# Key_Panel_030602.net
KiCad netlist of a schematic drawn in Altium Designer
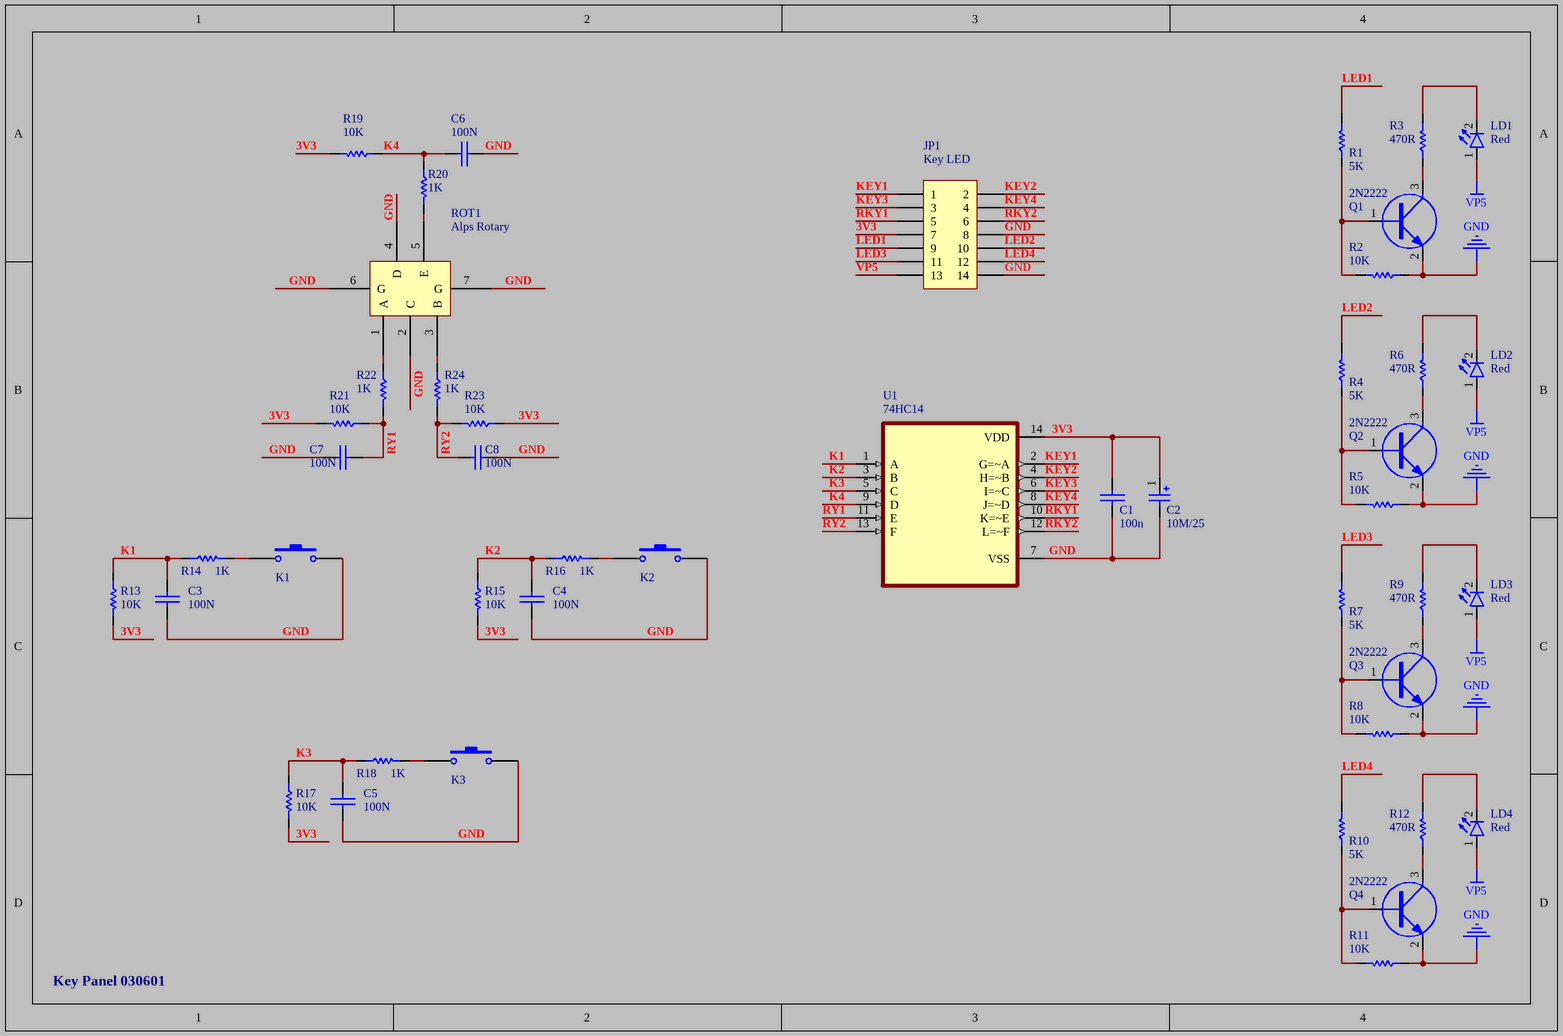
[diagram p0: Key Panel 030602.SchDoc]

(export (version "E")
  (design (tool "Eeschema 10.0.6"))
  (components
    (comp (ref "C1") (value "100n") (footprint "SMD_CAP_1206.") (libsource (lib "*") (part "C")))
    (comp (ref "C2")
      (value "10M/25")
      (footprint "CAP1p")
      (description "SMD Polarized Capacitor")
      (fields (field (name "PUBLISHER") "Altium Limited"))
      (libsource (lib "Mylibrary2019") (part "Cap Pol1 _ SMD"))
    )
    (comp (ref "C3") (value "100N") (footprint "SMD_CAP_1206.") (libsource (lib "*") (part "C")))
    (comp (ref "C4") (value "100N") (footprint "SMD_CAP_1206.") (libsource (lib "*") (part "C")))
    (comp (ref "C5") (value "100N") (footprint "SMD_CAP_1206.") (libsource (lib "*") (part "C")))
    (comp (ref "C6") (value "100N") (footprint "SMD_CAP_1206.") (libsource (lib "*") (part "C")))
    (comp (ref "C7") (value "100N") (footprint "SMD_CAP_1206.") (libsource (lib "*") (part "C")))
    (comp (ref "C8") (value "100N") (footprint "SMD_CAP_1206.") (libsource (lib "*") (part "C")))
    (comp (ref "JP1")
      (value "Key LED")
      (footprint "IDC14-BOX")
      (description "Header, 7-Pin, Dual row")
      (fields (field (name "PUBLISHER") "Altium Limited"))
      (libsource (lib "Miscellaneous Connectors") (part "Header 7X2"))
    )
    (comp (ref "K1")
      (value "Left")
      (footprint "SW-12*14")
      (description "Push Button Switch")
      (libsource (lib "My Library") (part "Switch PB"))
    )
    (comp (ref "K2")
      (value "Left")
      (footprint "SW-12*14")
      (description "Push Button Switch")
      (libsource (lib "My Library") (part "Switch PB"))
    )
    (comp (ref "K3")
      (value "Left")
      (footprint "SW-12*14")
      (description "Push Button Switch")
      (libsource (lib "My Library") (part "Switch PB"))
    )
    (comp (ref "LD1")
      (value "Red")
      (footprint "LED3")
      (description "LED")
      (fields (field (name "COLOR") "Red") (field (name "DESIGNER") "Saeid Jorablo"))
      (libsource (lib "My Library") (part "LED"))
    )
    (comp (ref "LD2")
      (value "Red")
      (footprint "LED3")
      (description "LED")
      (fields (field (name "COLOR") "Red") (field (name "DESIGNER") "Saeid Jorablo"))
      (libsource (lib "My Library") (part "LED"))
    )
    (comp (ref "LD3")
      (value "Red")
      (footprint "LED3")
      (description "LED")
      (fields (field (name "COLOR") "Red") (field (name "DESIGNER") "Saeid Jorablo"))
      (libsource (lib "My Library") (part "LED"))
    )
    (comp (ref "LD4")
      (value "Red")
      (footprint "LED3")
      (description "LED")
      (fields (field (name "COLOR") "Red") (field (name "DESIGNER") "Saeid Jorablo"))
      (libsource (lib "My Library") (part "LED"))
    )
    (comp (ref "Q1") (value "2N2222") (footprint "2N2222") (libsource (lib "1403 Schlib 2020") (part "N")))
    (comp (ref "Q2") (value "2N2222") (footprint "2N2222") (libsource (lib "1403 Schlib 2020") (part "N")))
    (comp (ref "Q3") (value "2N2222") (footprint "2N2222") (libsource (lib "1403 Schlib 2020") (part "N")))
    (comp (ref "Q4") (value "2N2222") (footprint "2N2222") (libsource (lib "1403 Schlib 2020") (part "N")))
    (comp (ref "R1")
      (value "5K")
      (footprint "RES 1206")
      (description "Resistor")
      (fields (field (name "TOLERANCE") "5%") (field (name "POWER") "1/8 W"))
      (libsource (lib "My Library") (part "Resistor"))
    )
    (comp (ref "R2")
      (value "10K")
      (footprint "RES 1206")
      (description "Resistor")
      (fields (field (name "TOLERANCE") "5%") (field (name "POWER") "1/8 W"))
      (libsource (lib "My Library") (part "Resistor"))
    )
    (comp (ref "R3")
      (value "470R")
      (footprint "RES 1206")
      (description "Resistor")
      (fields (field (name "TOLERANCE") "5%") (field (name "POWER") "1/8 W"))
      (libsource (lib "My Library") (part "Resistor"))
    )
    (comp (ref "R4")
      (value "5K")
      (footprint "RES 1206")
      (description "Resistor")
      (fields (field (name "TOLERANCE") "5%") (field (name "POWER") "1/8 W"))
      (libsource (lib "My Library") (part "Resistor"))
    )
    (comp (ref "R5")
      (value "10K")
      (footprint "RES 1206")
      (description "Resistor")
      (fields (field (name "TOLERANCE") "5%") (field (name "POWER") "1/8 W"))
      (libsource (lib "My Library") (part "Resistor"))
    )
    (comp (ref "R6")
      (value "470R")
      (footprint "RES 1206")
      (description "Resistor")
      (fields (field (name "TOLERANCE") "5%") (field (name "POWER") "1/8 W"))
      (libsource (lib "My Library") (part "Resistor"))
    )
    (comp (ref "R7")
      (value "5K")
      (footprint "RES 1206")
      (description "Resistor")
      (fields (field (name "TOLERANCE") "5%") (field (name "POWER") "1/8 W"))
      (libsource (lib "My Library") (part "Resistor"))
    )
    (comp (ref "R8")
      (value "10K")
      (footprint "RES 1206")
      (description "Resistor")
      (fields (field (name "TOLERANCE") "5%") (field (name "POWER") "1/8 W"))
      (libsource (lib "My Library") (part "Resistor"))
    )
    (comp (ref "R9")
      (value "470R")
      (footprint "RES 1206")
      (description "Resistor")
      (fields (field (name "TOLERANCE") "5%") (field (name "POWER") "1/8 W"))
      (libsource (lib "My Library") (part "Resistor"))
    )
    (comp (ref "R10")
      (value "5K")
      (footprint "RES 1206")
      (description "Resistor")
      (fields (field (name "TOLERANCE") "5%") (field (name "POWER") "1/8 W"))
      (libsource (lib "My Library") (part "Resistor"))
    )
    (comp (ref "R11")
      (value "10K")
      (footprint "RES 1206")
      (description "Resistor")
      (fields (field (name "TOLERANCE") "5%") (field (name "POWER") "1/8 W"))
      (libsource (lib "My Library") (part "Resistor"))
    )
    (comp (ref "R12")
      (value "470R")
      (footprint "RES 1206")
      (description "Resistor")
      (fields (field (name "TOLERANCE") "5%") (field (name "POWER") "1/8 W"))
      (libsource (lib "My Library") (part "Resistor"))
    )
    (comp (ref "R13")
      (value "10K")
      (footprint "RES 1206")
      (description "Resistor")
      (fields (field (name "TOLERANCE") "5%") (field (name "POWER") "1/8 W"))
      (libsource (lib "My Library") (part "Resistor"))
    )
    (comp (ref "R14")
      (value "1K")
      (footprint "RES 1206")
      (description "Resistor")
      (fields (field (name "TOLERANCE") "5%") (field (name "POWER") "1/8 W"))
      (libsource (lib "My Library") (part "Resistor"))
    )
    (comp (ref "R15")
      (value "10K")
      (footprint "RES 1206")
      (description "Resistor")
      (fields (field (name "TOLERANCE") "5%") (field (name "POWER") "1/8 W"))
      (libsource (lib "My Library") (part "Resistor"))
    )
    (comp (ref "R16")
      (value "1K")
      (footprint "RES 1206")
      (description "Resistor")
      (fields (field (name "TOLERANCE") "5%") (field (name "POWER") "1/8 W"))
      (libsource (lib "My Library") (part "Resistor"))
    )
    (comp (ref "R17")
      (value "10K")
      (footprint "RES 1206")
      (description "Resistor")
      (fields (field (name "TOLERANCE") "5%") (field (name "POWER") "1/8 W"))
      (libsource (lib "My Library") (part "Resistor"))
    )
    (comp (ref "R18")
      (value "1K")
      (footprint "RES 1206")
      (description "Resistor")
      (fields (field (name "TOLERANCE") "5%") (field (name "POWER") "1/8 W"))
      (libsource (lib "My Library") (part "Resistor"))
    )
    (comp (ref "R19")
      (value "10K")
      (footprint "RES 1206")
      (description "Resistor")
      (fields (field (name "TOLERANCE") "5%") (field (name "POWER") "1/8 W"))
      (libsource (lib "My Library") (part "Resistor"))
    )
    (comp (ref "R20")
      (value "1K")
      (footprint "RES 1206")
      (description "Resistor")
      (fields (field (name "TOLERANCE") "5%") (field (name "POWER") "1/8 W"))
      (libsource (lib "My Library") (part "Resistor"))
    )
    (comp (ref "R21")
      (value "10K")
      (footprint "RES 1206")
      (description "Resistor")
      (fields (field (name "TOLERANCE") "5%") (field (name "POWER") "1/8 W"))
      (libsource (lib "My Library") (part "Resistor"))
    )
    (comp (ref "R22")
      (value "1K")
      (footprint "RES 1206")
      (description "Resistor")
      (fields (field (name "TOLERANCE") "5%") (field (name "POWER") "1/8 W"))
      (libsource (lib "My Library") (part "Resistor"))
    )
    (comp (ref "R23")
      (value "10K")
      (footprint "RES 1206")
      (description "Resistor")
      (fields (field (name "TOLERANCE") "5%") (field (name "POWER") "1/8 W"))
      (libsource (lib "My Library") (part "Resistor"))
    )
    (comp (ref "R24")
      (value "1K")
      (footprint "RES 1206")
      (description "Resistor")
      (fields (field (name "TOLERANCE") "5%") (field (name "POWER") "1/8 W"))
      (libsource (lib "My Library") (part "Resistor"))
    )
    (comp (ref "ROT1")
      (value "Alps Rotary")
      (footprint "EC11")
      (libsource (lib "MyAltiumLib95") (part "AlpsRotary"))
    )
    (comp (ref "U1")
      (value "74HC14")
      (footprint "SOIC-14PIN")
      (description "CMOS Hex Schmitt Triggers 14-PDIP -55 to 125")
      (fields (field (name "MF") "Texas Instruments") (field (name "MP") "CD40106BE"))
      (libsource (lib "CD40106BE") (part "CD40106BE"))
    )
  )
  (nets
    (net (code "1") (name "/3V3") (class "Default")
      (node (ref "C1") (pin "2") (pintype "passive"))
      (node (ref "C2") (pin "1") (pinfunction "1_1") (pintype "passive"))
      (node (ref "JP1") (pin "7") (pinfunction "7_7") (pintype "passive"))
      (node (ref "R13") (pin "2") (pinfunction "2_2") (pintype "passive"))
      (node (ref "R15") (pin "2") (pinfunction "2_2") (pintype "passive"))
      (node (ref "R17") (pin "2") (pinfunction "2_2") (pintype "passive"))
      (node (ref "R19") (pin "2") (pinfunction "2_2") (pintype "passive"))
      (node (ref "R21") (pin "2") (pinfunction "2_2") (pintype "passive"))
      (node (ref "R23") (pin "1") (pinfunction "1_1") (pintype "passive"))
      (node (ref "U1") (pin "14") (pinfunction "VDD_14") (pintype "power_in"))
    )
    (net (code "2") (name "/K1") (class "Default")
      (node (ref "C3") (pin "2") (pintype "passive"))
      (node (ref "R13") (pin "1") (pinfunction "1_1") (pintype "passive"))
      (node (ref "R14") (pin "1") (pinfunction "1_1") (pintype "passive"))
      (node (ref "U1") (pin "1") (pinfunction "A_1") (pintype "input"))
    )
    (net (code "3") (name "/K2") (class "Default")
      (node (ref "C4") (pin "2") (pintype "passive"))
      (node (ref "R15") (pin "1") (pinfunction "1_1") (pintype "passive"))
      (node (ref "R16") (pin "1") (pinfunction "1_1") (pintype "passive"))
      (node (ref "U1") (pin "3") (pinfunction "B_3") (pintype "input"))
    )
    (net (code "4") (name "/K3") (class "Default")
      (node (ref "C5") (pin "2") (pintype "passive"))
      (node (ref "R17") (pin "1") (pinfunction "1_1") (pintype "passive"))
      (node (ref "R18") (pin "1") (pinfunction "1_1") (pintype "passive"))
      (node (ref "U1") (pin "5") (pinfunction "C_5") (pintype "input"))
    )
    (net (code "5") (name "/K4") (class "Default")
      (node (ref "C6") (pin "2") (pintype "passive"))
      (node (ref "R19") (pin "1") (pinfunction "1_1") (pintype "passive"))
      (node (ref "R20") (pin "1") (pinfunction "1_1") (pintype "passive"))
      (node (ref "U1") (pin "9") (pinfunction "D_9") (pintype "input"))
    )
    (net (code "6") (name "/KEY1") (class "Default")
      (node (ref "JP1") (pin "1") (pinfunction "1_1") (pintype "passive"))
      (node (ref "U1") (pin "2") (pinfunction "G=~A_2") (pintype "output"))
    )
    (net (code "7") (name "/KEY2") (class "Default")
      (node (ref "JP1") (pin "2") (pinfunction "2_2") (pintype "passive"))
      (node (ref "U1") (pin "4") (pinfunction "H=~B_4") (pintype "output"))
    )
    (net (code "8") (name "/KEY3") (class "Default")
      (node (ref "JP1") (pin "3") (pinfunction "3_3") (pintype "passive"))
      (node (ref "U1") (pin "6") (pinfunction "I=~C_6") (pintype "output"))
    )
    (net (code "9") (name "/KEY4") (class "Default")
      (node (ref "JP1") (pin "4") (pinfunction "4_4") (pintype "passive"))
      (node (ref "U1") (pin "8") (pinfunction "J=~D_8") (pintype "output"))
    )
    (net (code "10") (name "/LED1") (class "Default")
      (node (ref "JP1") (pin "9") (pinfunction "9_9") (pintype "passive"))
      (node (ref "R1") (pin "2") (pinfunction "2_2") (pintype "passive"))
    )
    (net (code "11") (name "/LED2") (class "Default")
      (node (ref "JP1") (pin "10") (pinfunction "10_10") (pintype "passive"))
      (node (ref "R4") (pin "2") (pinfunction "2_2") (pintype "passive"))
    )
    (net (code "12") (name "/LED3") (class "Default")
      (node (ref "JP1") (pin "11") (pinfunction "11_11") (pintype "passive"))
      (node (ref "R7") (pin "2") (pinfunction "2_2") (pintype "passive"))
    )
    (net (code "13") (name "/LED4") (class "Default")
      (node (ref "JP1") (pin "12") (pinfunction "12_12") (pintype "passive"))
      (node (ref "R10") (pin "2") (pinfunction "2_2") (pintype "passive"))
    )
    (net (code "14") (name "/RKY1") (class "Default")
      (node (ref "JP1") (pin "5") (pinfunction "5_5") (pintype "passive"))
      (node (ref "U1") (pin "10") (pinfunction "K=~E_10") (pintype "output"))
    )
    (net (code "15") (name "/RKY2") (class "Default")
      (node (ref "JP1") (pin "6") (pinfunction "6_6") (pintype "passive"))
      (node (ref "U1") (pin "12") (pinfunction "L=~F_12") (pintype "output"))
    )
    (net (code "16") (name "/RY1") (class "Default")
      (node (ref "C7") (pin "2") (pintype "passive"))
      (node (ref "R21") (pin "1") (pinfunction "1_1") (pintype "passive"))
      (node (ref "R22") (pin "2") (pinfunction "2_2") (pintype "passive"))
      (node (ref "U1") (pin "11") (pinfunction "E_11") (pintype "input"))
    )
    (net (code "17") (name "/RY2") (class "Default")
      (node (ref "C8") (pin "2") (pintype "passive"))
      (node (ref "R23") (pin "2") (pinfunction "2_2") (pintype "passive"))
      (node (ref "R24") (pin "2") (pinfunction "2_2") (pintype "passive"))
      (node (ref "U1") (pin "13") (pinfunction "F_13") (pintype "input"))
    )
    (net (code "18") (name "GND") (class "Default")
      (node (ref "C1") (pin "1") (pintype "passive"))
      (node (ref "C2") (pin "2") (pinfunction "2_2") (pintype "passive"))
      (node (ref "C3") (pin "1") (pintype "passive"))
      (node (ref "C4") (pin "1") (pintype "passive"))
      (node (ref "C5") (pin "1") (pintype "passive"))
      (node (ref "C6") (pin "1") (pintype "passive"))
      (node (ref "C7") (pin "1") (pintype "passive"))
      (node (ref "C8") (pin "1") (pintype "passive"))
      (node (ref "JP1") (pin "14") (pinfunction "14_14") (pintype "passive"))
      (node (ref "JP1") (pin "8") (pinfunction "8_8") (pintype "passive"))
      (node (ref "K1") (pin "2") (pinfunction "2_2") (pintype "passive"))
      (node (ref "K2") (pin "2") (pinfunction "2_2") (pintype "passive"))
      (node (ref "K3") (pin "2") (pinfunction "2_2") (pintype "passive"))
      (node (ref "Q1") (pin "2") (pinfunction "B_2") (pintype "passive"))
      (node (ref "Q2") (pin "2") (pinfunction "B_2") (pintype "passive"))
      (node (ref "Q3") (pin "2") (pinfunction "B_2") (pintype "passive"))
      (node (ref "Q4") (pin "2") (pinfunction "B_2") (pintype "passive"))
      (node (ref "R11") (pin "1") (pinfunction "1_1") (pintype "passive"))
      (node (ref "R2") (pin "1") (pinfunction "1_1") (pintype "passive"))
      (node (ref "R5") (pin "1") (pinfunction "1_1") (pintype "passive"))
      (node (ref "R8") (pin "1") (pinfunction "1_1") (pintype "passive"))
      (node (ref "ROT1") (pin "2") (pinfunction "C_2") (pintype "passive"))
      (node (ref "ROT1") (pin "4") (pinfunction "D_4") (pintype "passive"))
      (node (ref "ROT1") (pin "6") (pinfunction "G_6") (pintype "passive"))
      (node (ref "ROT1") (pin "7") (pinfunction "G_7") (pintype "passive"))
      (node (ref "U1") (pin "7") (pinfunction "VSS_7") (pintype "power_in"))
    )
    (net (code "19") (name "Net-(K1-Pad1)") (class "Default")
      (node (ref "K1") (pin "1") (pinfunction "1_1") (pintype "passive"))
      (node (ref "R14") (pin "2") (pinfunction "2_2") (pintype "passive"))
    )
    (net (code "20") (name "Net-(K2-Pad1)") (class "Default")
      (node (ref "K2") (pin "1") (pinfunction "1_1") (pintype "passive"))
      (node (ref "R16") (pin "2") (pinfunction "2_2") (pintype "passive"))
    )
    (net (code "21") (name "Net-(K3-Pad1)") (class "Default")
      (node (ref "K3") (pin "1") (pinfunction "1_1") (pintype "passive"))
      (node (ref "R18") (pin "2") (pinfunction "2_2") (pintype "passive"))
    )
    (net (code "22") (name "Net-(LD1-K)") (class "Default")
      (node (ref "LD1") (pin "2") (pinfunction "K_2") (pintype "passive"))
      (node (ref "R3") (pin "2") (pinfunction "2_2") (pintype "passive"))
    )
    (net (code "23") (name "Net-(LD2-K)") (class "Default")
      (node (ref "LD2") (pin "2") (pinfunction "K_2") (pintype "passive"))
      (node (ref "R6") (pin "2") (pinfunction "2_2") (pintype "passive"))
    )
    (net (code "24") (name "Net-(LD3-K)") (class "Default")
      (node (ref "LD3") (pin "2") (pinfunction "K_2") (pintype "passive"))
      (node (ref "R9") (pin "2") (pinfunction "2_2") (pintype "passive"))
    )
    (net (code "25") (name "Net-(LD4-K)") (class "Default")
      (node (ref "LD4") (pin "2") (pinfunction "K_2") (pintype "passive"))
      (node (ref "R12") (pin "2") (pinfunction "2_2") (pintype "passive"))
    )
    (net (code "26") (name "Net-(Q1-C)") (class "Default")
      (node (ref "Q1") (pin "3") (pinfunction "C_3") (pintype "passive"))
      (node (ref "R3") (pin "1") (pinfunction "1_1") (pintype "passive"))
    )
    (net (code "27") (name "Net-(Q1-E)") (class "Default")
      (node (ref "Q1") (pin "1") (pinfunction "E_1") (pintype "passive"))
      (node (ref "R1") (pin "1") (pinfunction "1_1") (pintype "passive"))
      (node (ref "R2") (pin "2") (pinfunction "2_2") (pintype "passive"))
    )
    (net (code "28") (name "Net-(Q2-C)") (class "Default")
      (node (ref "Q2") (pin "3") (pinfunction "C_3") (pintype "passive"))
      (node (ref "R6") (pin "1") (pinfunction "1_1") (pintype "passive"))
    )
    (net (code "29") (name "Net-(Q2-E)") (class "Default")
      (node (ref "Q2") (pin "1") (pinfunction "E_1") (pintype "passive"))
      (node (ref "R4") (pin "1") (pinfunction "1_1") (pintype "passive"))
      (node (ref "R5") (pin "2") (pinfunction "2_2") (pintype "passive"))
    )
    (net (code "30") (name "Net-(Q3-C)") (class "Default")
      (node (ref "Q3") (pin "3") (pinfunction "C_3") (pintype "passive"))
      (node (ref "R9") (pin "1") (pinfunction "1_1") (pintype "passive"))
    )
    (net (code "31") (name "Net-(Q3-E)") (class "Default")
      (node (ref "Q3") (pin "1") (pinfunction "E_1") (pintype "passive"))
      (node (ref "R7") (pin "1") (pinfunction "1_1") (pintype "passive"))
      (node (ref "R8") (pin "2") (pinfunction "2_2") (pintype "passive"))
    )
    (net (code "32") (name "Net-(Q4-C)") (class "Default")
      (node (ref "Q4") (pin "3") (pinfunction "C_3") (pintype "passive"))
      (node (ref "R12") (pin "1") (pinfunction "1_1") (pintype "passive"))
    )
    (net (code "33") (name "Net-(Q4-E)") (class "Default")
      (node (ref "Q4") (pin "1") (pinfunction "E_1") (pintype "passive"))
      (node (ref "R10") (pin "1") (pinfunction "1_1") (pintype "passive"))
      (node (ref "R11") (pin "2") (pinfunction "2_2") (pintype "passive"))
    )
    (net (code "34") (name "Net-(ROT1-A)") (class "Default")
      (node (ref "R22") (pin "1") (pinfunction "1_1") (pintype "passive"))
      (node (ref "ROT1") (pin "1") (pinfunction "A_1") (pintype "passive"))
    )
    (net (code "35") (name "Net-(ROT1-B)") (class "Default")
      (node (ref "R24") (pin "1") (pinfunction "1_1") (pintype "passive"))
      (node (ref "ROT1") (pin "3") (pinfunction "B_3") (pintype "passive"))
    )
    (net (code "36") (name "Net-(ROT1-E)") (class "Default")
      (node (ref "R20") (pin "2") (pinfunction "2_2") (pintype "passive"))
      (node (ref "ROT1") (pin "5") (pinfunction "E_5") (pintype "passive"))
    )
    (net (code "37") (name "VP5") (class "Default")
      (node (ref "JP1") (pin "13") (pinfunction "13_13") (pintype "passive"))
      (node (ref "LD1") (pin "1") (pinfunction "A_1") (pintype "passive"))
      (node (ref "LD2") (pin "1") (pinfunction "A_1") (pintype "passive"))
      (node (ref "LD3") (pin "1") (pinfunction "A_1") (pintype "passive"))
      (node (ref "LD4") (pin "1") (pinfunction "A_1") (pintype "passive"))
    )
  )
)
